# Pure_Keys_aec-pcb3-smd-Vertical-inProgre.net
KiCad netlist of a schematic drawn in EAGLE
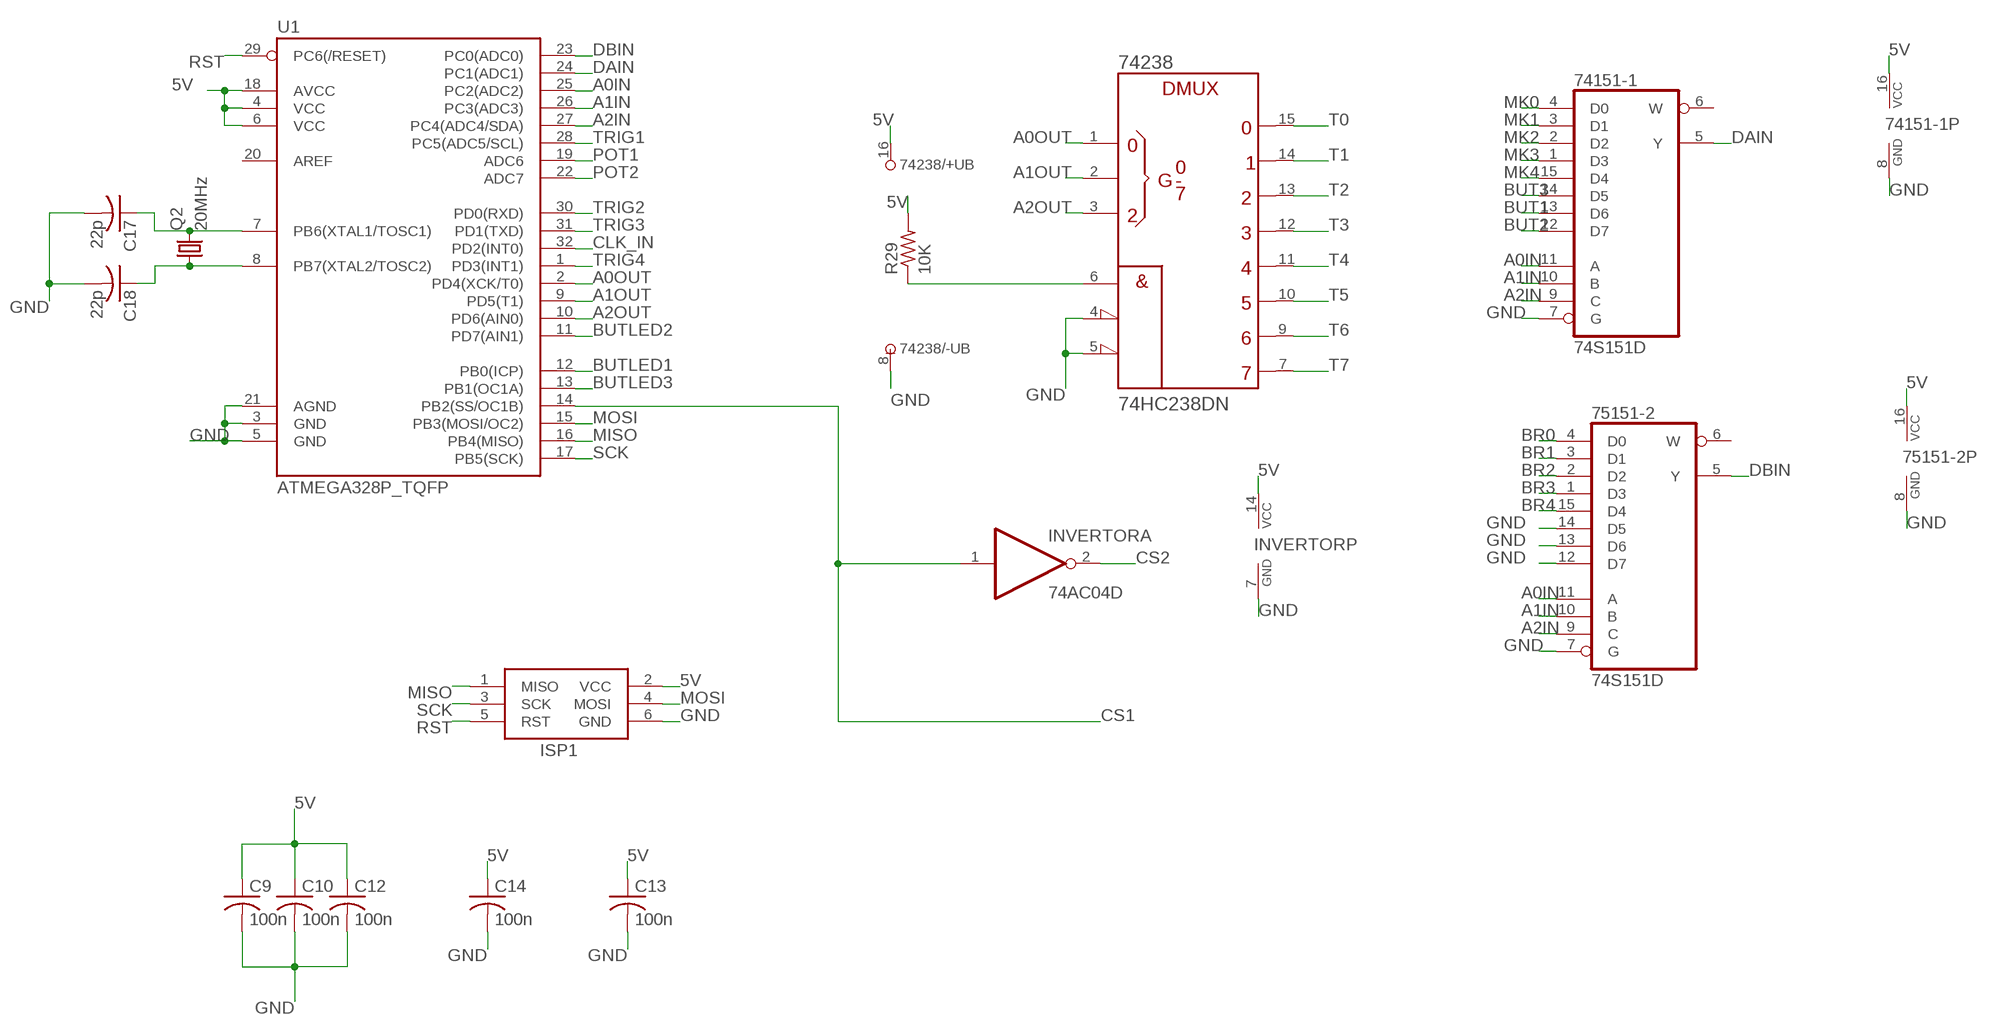
[diagram p0: schematic, sheet 1]
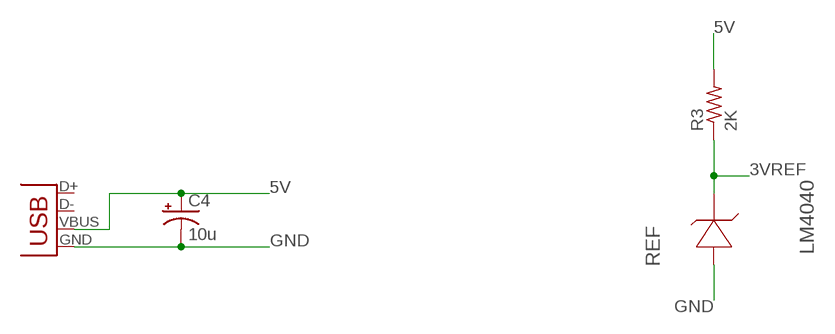
[diagram p1: schematic, sheet 2]
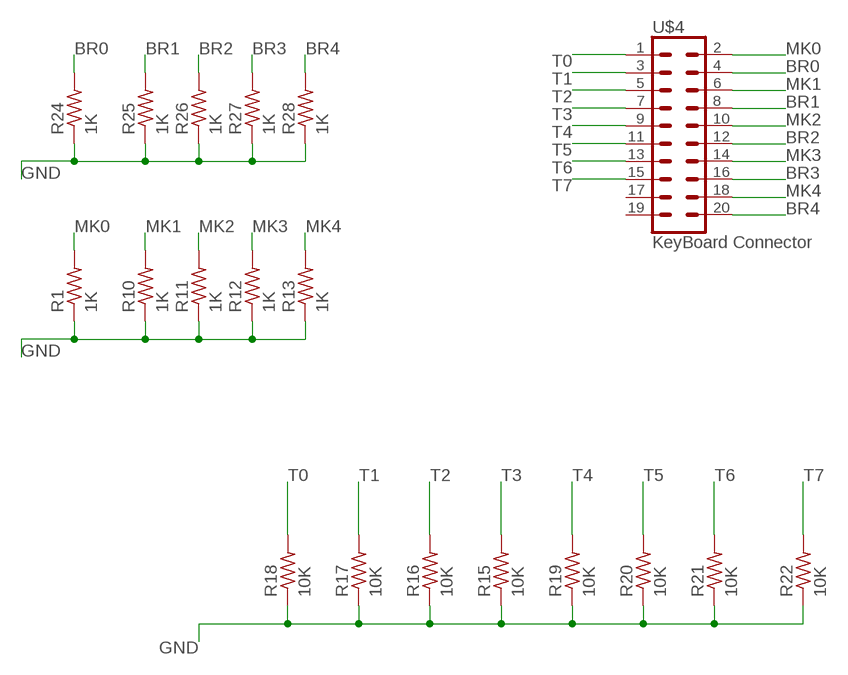
[diagram p2: schematic, sheet 3]
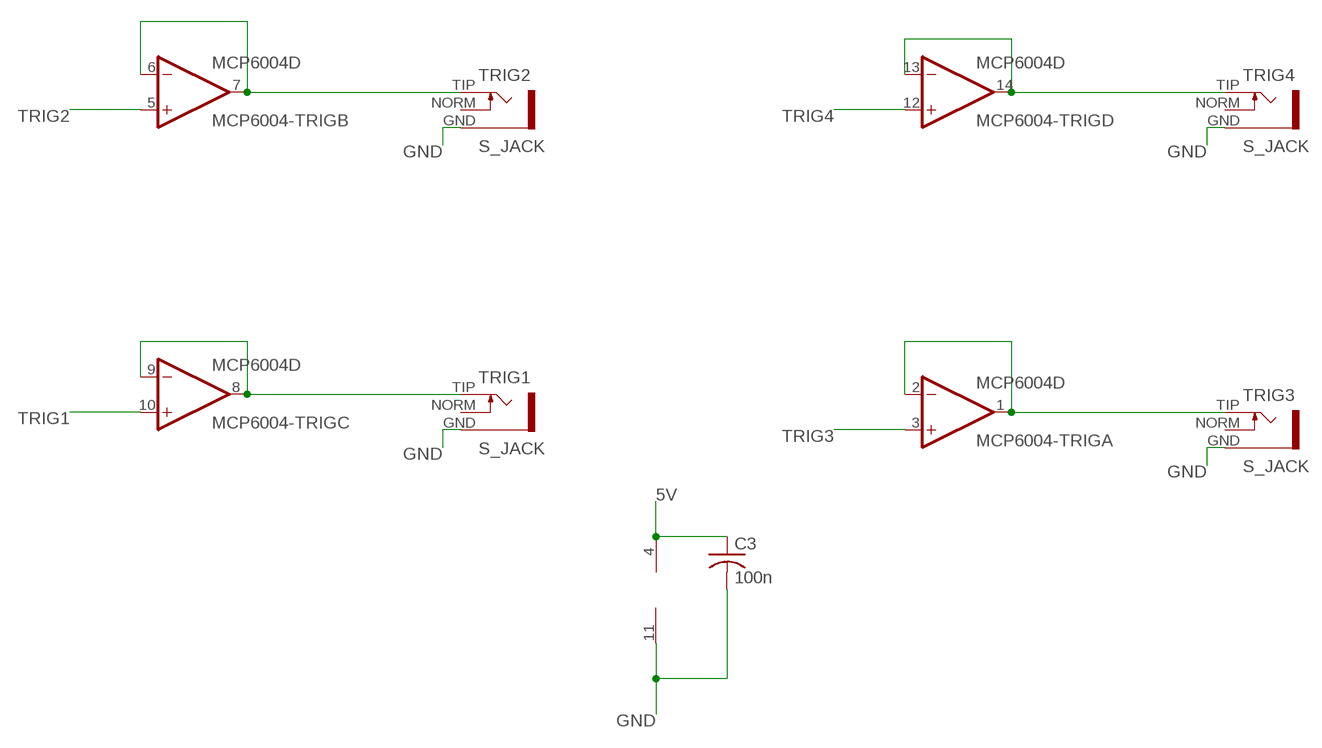
[diagram p3: schematic, sheet 4]
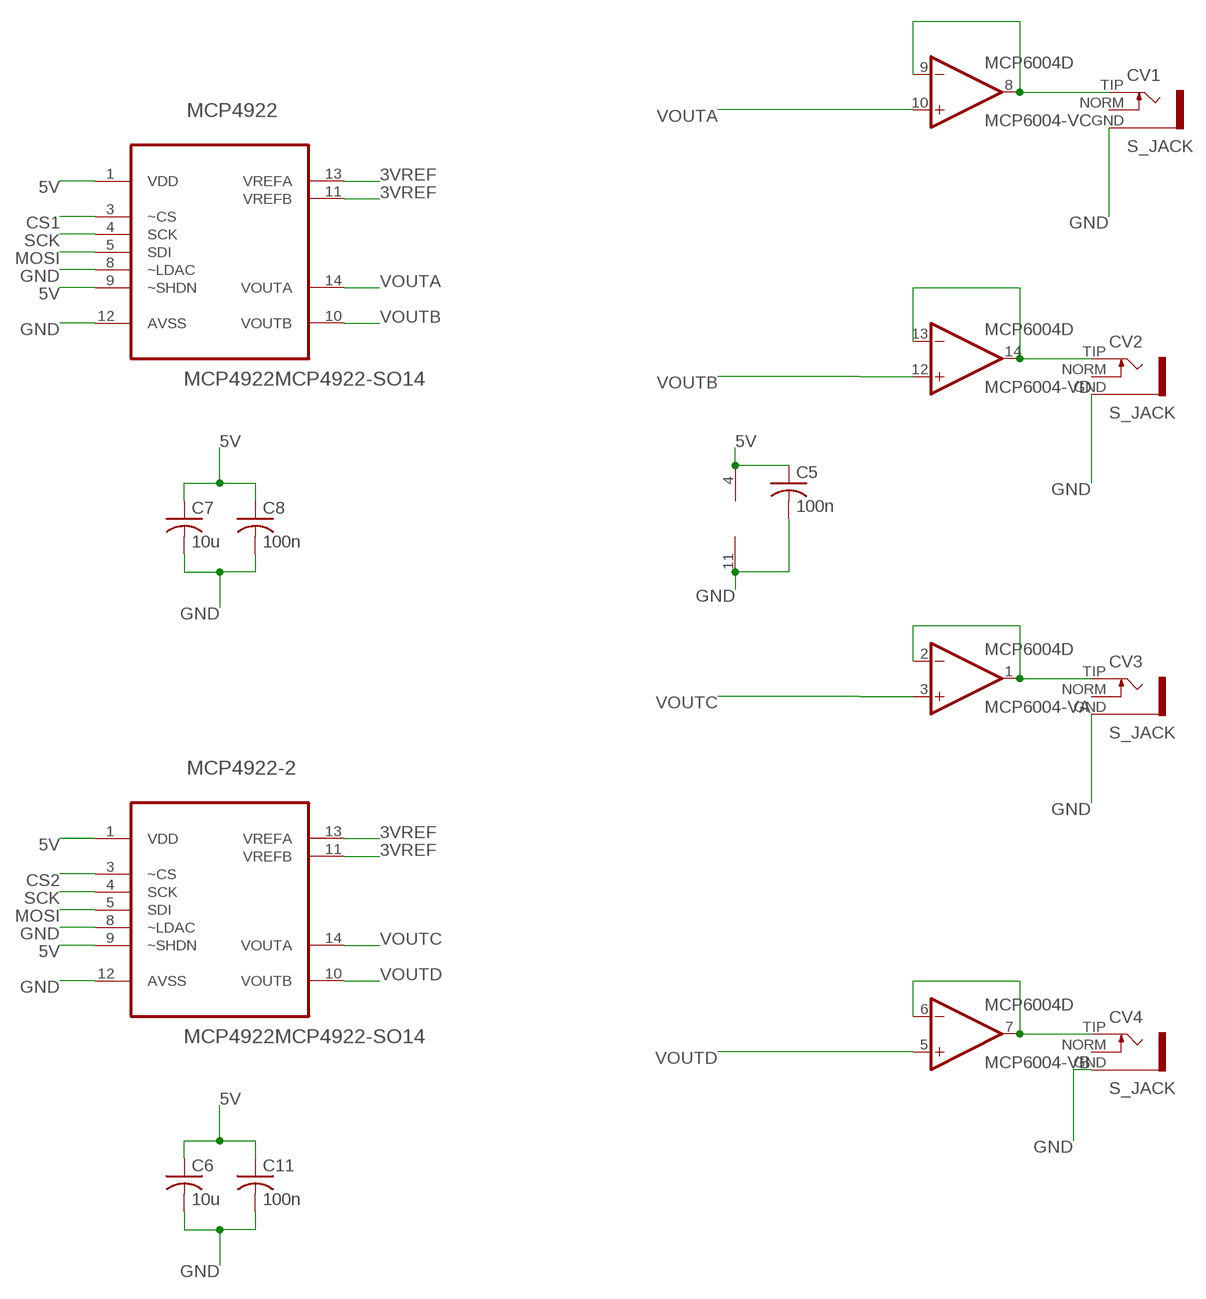
[diagram p4: schematic, sheet 5]
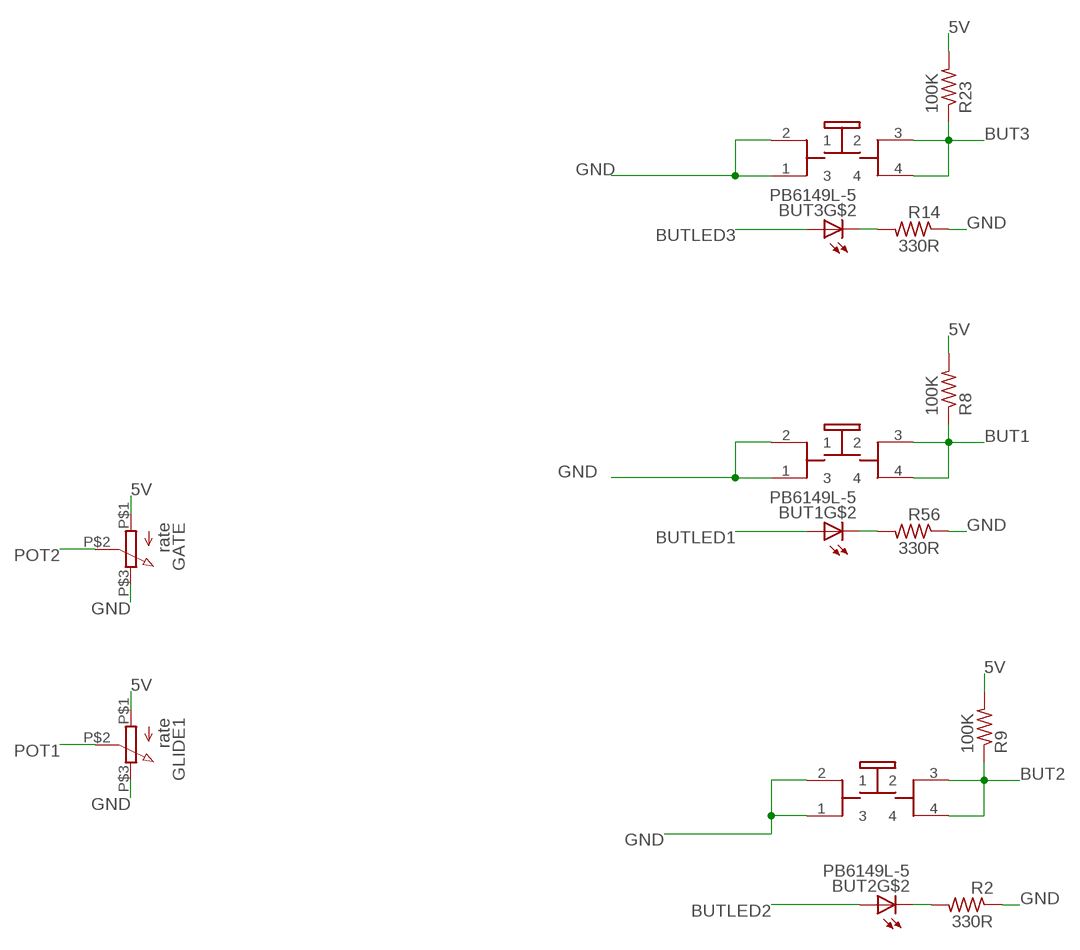
[diagram p5: schematic, sheet 6]
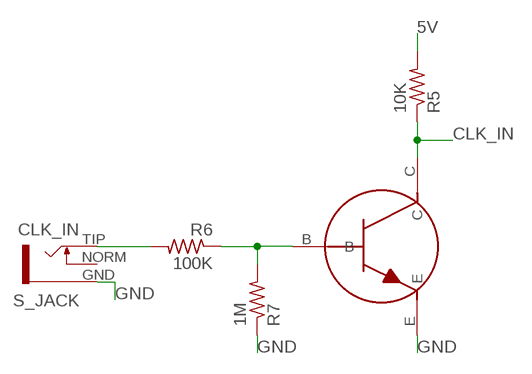
[diagram p6: schematic, sheet 7]

(export (version "E")
  (design (tool "Eeschema 10.0.6"))
  (components
    (comp (ref "C5")
      (value "100n")
      (footprint "eagle-import:C0805K")
      (libsource (lib "eagle-import") (part "C-USC0805K"))
    )
    (comp (ref "C6")
      (value "10u")
      (footprint "eagle-import:C0805K")
      (libsource (lib "eagle-import") (part "C-USC0805K"))
    )
    (comp (ref "C7")
      (value "10u")
      (footprint "eagle-import:C0805K")
      (libsource (lib "eagle-import") (part "C-USC0805K"))
    )
    (comp (ref "C8")
      (value "100n")
      (footprint "eagle-import:C0805K")
      (libsource (lib "eagle-import") (part "C-USC0805K"))
    )
    (comp (ref "C11")
      (value "100n")
      (footprint "eagle-import:C0805K")
      (libsource (lib "eagle-import") (part "C-USC0805K"))
    )
    (comp (ref "CV1")
      (value "S_JACK")
      (footprint "eagle-import:S_JACK")
      (libsource (lib "eagle-import") (part "S_JACK"))
    )
    (comp (ref "CV2")
      (value "S_JACK")
      (footprint "eagle-import:S_JACK")
      (libsource (lib "eagle-import") (part "S_JACK"))
    )
    (comp (ref "CV3")
      (value "S_JACK")
      (footprint "eagle-import:S_JACK")
      (libsource (lib "eagle-import") (part "S_JACK"))
    )
    (comp (ref "CV4")
      (value "S_JACK")
      (footprint "eagle-import:S_JACK")
      (libsource (lib "eagle-import") (part "S_JACK"))
    )
    (comp (ref "MCP4922")
      (value "MCP4922MCP4922-SO14")
      (footprint "eagle-import:SO14")
      (libsource (lib "eagle-import") (part "MCP4922MCP4922-SO14"))
    )
    (comp (ref "MCP4922-2")
      (value "MCP4922MCP4922-SO14")
      (footprint "eagle-import:SO14")
      (libsource (lib "eagle-import") (part "MCP4922MCP4922-SO14"))
    )
    (comp (ref "MCP6004-V")
      (value "MCP6004D")
      (footprint "eagle-import:SO14")
      (libsource (lib "eagle-import") (part "MCP6004D"))
    )
    (comp (ref "74151-1")
      (value "74S151D")
      (footprint "eagle-import:SO16")
      (libsource (lib "eagle-import") (part "74151DS"))
    )
    (comp (ref "74238")
      (value "74HC238DN")
      (footprint "eagle-import:SO16")
      (libsource (lib "eagle-import") (part "74HC238DN"))
    )
    (comp (ref "75151-2")
      (value "74S151D")
      (footprint "eagle-import:SO16")
      (libsource (lib "eagle-import") (part "74151DS"))
    )
    (comp (ref "C9")
      (value "100n")
      (footprint "eagle-import:C0805K")
      (libsource (lib "eagle-import") (part "C-USC0805K"))
    )
    (comp (ref "C10")
      (value "100n")
      (footprint "eagle-import:C0805K")
      (libsource (lib "eagle-import") (part "C-USC0805K"))
    )
    (comp (ref "C12")
      (value "100n")
      (footprint "eagle-import:C0805K")
      (libsource (lib "eagle-import") (part "C-USC0805K"))
    )
    (comp (ref "C13")
      (value "100n")
      (footprint "eagle-import:C0805K")
      (libsource (lib "eagle-import") (part "C-USC0805K"))
    )
    (comp (ref "C14")
      (value "100n")
      (footprint "eagle-import:C0805K")
      (libsource (lib "eagle-import") (part "C-USC0805K"))
    )
    (comp (ref "C17")
      (value "22p")
      (footprint "eagle-import:C0805K")
      (libsource (lib "eagle-import") (part "C-USC0805K"))
    )
    (comp (ref "C18")
      (value "22p")
      (footprint "eagle-import:C0805K")
      (libsource (lib "eagle-import") (part "C-USC0805K"))
    )
    (comp (ref "INVERTOR")
      (value "74AC04D")
      (footprint "eagle-import:SO14")
      (libsource (lib "eagle-import") (part "7404DAC"))
    )
    (comp (ref "ISP1")
      (value "AVRISP-6")
      (footprint "eagle-import:AVRISP")
      (libsource (lib "eagle-import") (part "AVRISP-6"))
    )
    (comp (ref "Q2")
      (value "20MHz")
      (footprint "eagle-import:HC49UP")
      (libsource (lib "eagle-import") (part "CRYSTALHC49UP"))
    )
    (comp (ref "R29")
      (value "10K")
      (footprint "eagle-import:R0805")
      (libsource (lib "eagle-import") (part "R-US_R0805"))
    )
    (comp (ref "U1")
      (value "ATMEGA328P_TQFP")
      (footprint "eagle-import:TQFP32-08")
      (libsource (lib "eagle-import") (part "ATMEGA328P_TQFP"))
    )
    (comp (ref "C4")
      (value "10u")
      (footprint "eagle-import:153CLV-0505")
      (libsource (lib "eagle-import") (part "CPOL-US153CLV-0505"))
    )
    (comp (ref "JP2")
      (value "USB-B")
      (footprint "eagle-import:USB-B-PTH")
      (libsource (lib "eagle-import") (part "USBPTH"))
    )
    (comp (ref "R3")
      (value "2K")
      (footprint "eagle-import:R0805")
      (libsource (lib "eagle-import") (part "R-US_R0805"))
    )
    (comp (ref "REF")
      (value "LM4040")
      (footprint "eagle-import:SOT95P237X112-3N")
      (fields
        (field (name "MPN") "LM4040A50IDBZT")
        (field (name "MPN_1") "LM4040A30IDBZT")
        (field (name "RS-PART") "809-6343")
      )
      (libsource (lib "eagle-import") (part "LM4040A30IDBZT"))
    )
    (comp (ref "CLK_IN")
      (value "S_JACK")
      (footprint "eagle-import:S_JACK")
      (libsource (lib "eagle-import") (part "S_JACK"))
    )
    (comp (ref "CLOCK")
      (value "2N3904")
      (footprint "eagle-import:TRANSISTOR_SINGLE_N-TYPE")
      (libsource (lib "eagle-import") (part "TRANSISTOR_MMBT3904"))
    )
    (comp (ref "R5")
      (value "10K")
      (footprint "eagle-import:R0805")
      (libsource (lib "eagle-import") (part "R-US_R0805"))
    )
    (comp (ref "R6")
      (value "100K")
      (footprint "eagle-import:R0805")
      (libsource (lib "eagle-import") (part "R-US_R0805"))
    )
    (comp (ref "R7")
      (value "1M")
      (footprint "eagle-import:R0805")
      (libsource (lib "eagle-import") (part "R-US_R0805"))
    )
    (comp (ref "R1")
      (value "1K")
      (footprint "eagle-import:R0805")
      (fields (field (name "RS-PART") "223-0427"))
      (libsource (lib "eagle-import") (part "R-US_R0805"))
    )
    (comp (ref "R10")
      (value "1K")
      (footprint "eagle-import:R0805")
      (fields (field (name "RS-PART") "223-0427"))
      (libsource (lib "eagle-import") (part "R-US_R0805"))
    )
    (comp (ref "R11")
      (value "1K")
      (footprint "eagle-import:R0805")
      (fields (field (name "RS-PART") "223-0427"))
      (libsource (lib "eagle-import") (part "R-US_R0805"))
    )
    (comp (ref "R12")
      (value "1K")
      (footprint "eagle-import:R0805")
      (fields (field (name "RS-PART") "223-0427"))
      (libsource (lib "eagle-import") (part "R-US_R0805"))
    )
    (comp (ref "R13")
      (value "1K")
      (footprint "eagle-import:R0805")
      (fields (field (name "RS-PART") "223-0427"))
      (libsource (lib "eagle-import") (part "R-US_R0805"))
    )
    (comp (ref "R15")
      (value "10K")
      (footprint "eagle-import:R0805")
      (libsource (lib "eagle-import") (part "R-US_R0805"))
    )
    (comp (ref "R16")
      (value "10K")
      (footprint "eagle-import:R0805")
      (libsource (lib "eagle-import") (part "R-US_R0805"))
    )
    (comp (ref "R17")
      (value "10K")
      (footprint "eagle-import:R0805")
      (libsource (lib "eagle-import") (part "R-US_R0805"))
    )
    (comp (ref "R18")
      (value "10K")
      (footprint "eagle-import:R0805")
      (libsource (lib "eagle-import") (part "R-US_R0805"))
    )
    (comp (ref "R19")
      (value "10K")
      (footprint "eagle-import:R0805")
      (libsource (lib "eagle-import") (part "R-US_R0805"))
    )
    (comp (ref "R20")
      (value "10K")
      (footprint "eagle-import:R0805")
      (libsource (lib "eagle-import") (part "R-US_R0805"))
    )
    (comp (ref "R21")
      (value "10K")
      (footprint "eagle-import:R0805")
      (libsource (lib "eagle-import") (part "R-US_R0805"))
    )
    (comp (ref "R22")
      (value "10K")
      (footprint "eagle-import:R0805")
      (libsource (lib "eagle-import") (part "R-US_R0805"))
    )
    (comp (ref "R24")
      (value "1K")
      (footprint "eagle-import:R0805")
      (fields (field (name "RS-PART") "223-0427"))
      (libsource (lib "eagle-import") (part "R-US_R0805"))
    )
    (comp (ref "R25")
      (value "1K")
      (footprint "eagle-import:R0805")
      (fields (field (name "RS-PART") "223-0427"))
      (libsource (lib "eagle-import") (part "R-US_R0805"))
    )
    (comp (ref "R26")
      (value "1K")
      (footprint "eagle-import:R0805")
      (fields (field (name "RS-PART") "223-0427"))
      (libsource (lib "eagle-import") (part "R-US_R0805"))
    )
    (comp (ref "R27")
      (value "1K")
      (footprint "eagle-import:R0805")
      (fields (field (name "RS-PART") "223-0427"))
      (libsource (lib "eagle-import") (part "R-US_R0805"))
    )
    (comp (ref "R28")
      (value "1K")
      (footprint "eagle-import:R0805")
      (fields (field (name "RS-PART") "223-0427"))
      (libsource (lib "eagle-import") (part "R-US_R0805"))
    )
    (comp (ref "U$4")
      (value "KeyBoard Connector")
      (footprint "eagle-import:2X10")
      (fields (field (name "RS-PART") "669-5364"))
      (libsource (lib "eagle-import") (part "CONN_10X2"))
    )
    (comp (ref "BUT1")
      (value "PB6149L-5")
      (footprint "eagle-import:PB6149L")
      (libsource (lib "eagle-import") (part "PB6149L-5"))
    )
    (comp (ref "BUT2")
      (value "PB6149L-5")
      (footprint "eagle-import:PB6149L")
      (libsource (lib "eagle-import") (part "PB6149L-5"))
    )
    (comp (ref "BUT3")
      (value "PB6149L-5")
      (footprint "eagle-import:PB6149L")
      (libsource (lib "eagle-import") (part "PB6149L-5"))
    )
    (comp (ref "GATE")
      (value "rate")
      (footprint "eagle-import:POT")
      (libsource (lib "eagle-import") (part "9MMPOT"))
    )
    (comp (ref "GLIDE1")
      (value "rate")
      (footprint "eagle-import:POT")
      (libsource (lib "eagle-import") (part "9MMPOT"))
    )
    (comp (ref "R2")
      (value "330R")
      (footprint "eagle-import:R0805")
      (libsource (lib "eagle-import") (part "R-US_R0805"))
    )
    (comp (ref "R8")
      (value "100K")
      (footprint "eagle-import:R0805")
      (libsource (lib "eagle-import") (part "R-US_R0805"))
    )
    (comp (ref "R9")
      (value "100K")
      (footprint "eagle-import:R0805")
      (libsource (lib "eagle-import") (part "R-US_R0805"))
    )
    (comp (ref "R14")
      (value "330R")
      (footprint "eagle-import:R0805")
      (libsource (lib "eagle-import") (part "R-US_R0805"))
    )
    (comp (ref "R23")
      (value "100K")
      (footprint "eagle-import:R0805")
      (libsource (lib "eagle-import") (part "R-US_R0805"))
    )
    (comp (ref "R56")
      (value "330R")
      (footprint "eagle-import:R0805")
      (libsource (lib "eagle-import") (part "R-US_R0805"))
    )
    (comp (ref "C3")
      (value "100n")
      (footprint "eagle-import:C0805K")
      (libsource (lib "eagle-import") (part "C-USC0805K"))
    )
    (comp (ref "MCP6004-TRIG")
      (value "MCP6004D")
      (footprint "eagle-import:SO14")
      (libsource (lib "eagle-import") (part "MCP6004D"))
    )
    (comp (ref "TRIG1")
      (value "S_JACK")
      (footprint "eagle-import:S_JACK")
      (libsource (lib "eagle-import") (part "S_JACK"))
    )
    (comp (ref "TRIG2")
      (value "S_JACK")
      (footprint "eagle-import:S_JACK")
      (libsource (lib "eagle-import") (part "S_JACK"))
    )
    (comp (ref "TRIG3")
      (value "S_JACK")
      (footprint "eagle-import:S_JACK")
      (libsource (lib "eagle-import") (part "S_JACK"))
    )
    (comp (ref "TRIG4")
      (value "S_JACK")
      (footprint "eagle-import:S_JACK")
      (libsource (lib "eagle-import") (part "S_JACK"))
    )
  )
  (nets
    (net (code "1") (name "3VREF") (class "Default")
      (node (ref "MCP4922") (pin "11") (pinfunction "VREFB_11") (pintype "bidirectional"))
      (node (ref "MCP4922") (pin "13") (pinfunction "VREFA_13") (pintype "input"))
      (node (ref "MCP4922-2") (pin "11") (pinfunction "VREFB_11") (pintype "bidirectional"))
      (node (ref "MCP4922-2") (pin "13") (pinfunction "VREFA_13") (pintype "input"))
      (node (ref "R3") (pin "1") (pinfunction "1_1") (pintype "passive"))
      (node (ref "REF") (pin "1") (pinfunction "CATHODE_1") (pintype "output"))
    )
    (net (code "2") (name "5V") (class "Default")
      (node (ref "74151-1") (pin "16") (pinfunction "VCC_16") (pintype "power_in"))
      (node (ref "74238") (pin "16") (pinfunction "+UB_16") (pintype "power_in"))
      (node (ref "75151-2") (pin "16") (pinfunction "VCC_16") (pintype "power_in"))
      (node (ref "C10") (pin "1") (pinfunction "1_1") (pintype "passive"))
      (node (ref "C11") (pin "1") (pinfunction "1_1") (pintype "passive"))
      (node (ref "C12") (pin "1") (pinfunction "1_1") (pintype "passive"))
      (node (ref "C13") (pin "1") (pinfunction "1_1") (pintype "passive"))
      (node (ref "C14") (pin "1") (pinfunction "1_1") (pintype "passive"))
      (node (ref "C3") (pin "1") (pinfunction "1_1") (pintype "passive"))
      (node (ref "C4") (pin "+") (pinfunction "+_+") (pintype "passive"))
      (node (ref "C5") (pin "1") (pinfunction "1_1") (pintype "passive"))
      (node (ref "C6") (pin "1") (pinfunction "1_1") (pintype "passive"))
      (node (ref "C7") (pin "1") (pinfunction "1_1") (pintype "passive"))
      (node (ref "C8") (pin "1") (pinfunction "1_1") (pintype "passive"))
      (node (ref "C9") (pin "1") (pinfunction "1_1") (pintype "passive"))
      (node (ref "GATE") (pin "P$1") (pinfunction "1_P$1") (pintype "passive"))
      (node (ref "GLIDE1") (pin "P$1") (pinfunction "1_P$1") (pintype "passive"))
      (node (ref "INVERTOR") (pin "14") (pinfunction "VCC_14") (pintype "power_in"))
      (node (ref "ISP1") (pin "2") (pinfunction "VCC_2") (pintype "power_in"))
      (node (ref "JP2") (pin "VBUS") (pinfunction "VBUS_VBUS") (pintype "bidirectional"))
      (node (ref "MCP4922") (pin "1") (pinfunction "VDD_1") (pintype "power_in"))
      (node (ref "MCP4922") (pin "9") (pinfunction "~{SHDN}_9") (pintype "bidirectional"))
      (node (ref "MCP4922-2") (pin "1") (pinfunction "VDD_1") (pintype "power_in"))
      (node (ref "MCP4922-2") (pin "9") (pinfunction "~{SHDN}_9") (pintype "bidirectional"))
      (node (ref "MCP6004-TRIG") (pin "4") (pinfunction "V+_4") (pintype "power_in"))
      (node (ref "MCP6004-V") (pin "4") (pinfunction "V+_4") (pintype "power_in"))
      (node (ref "R23") (pin "2") (pinfunction "2_2") (pintype "passive"))
      (node (ref "R29") (pin "2") (pinfunction "2_2") (pintype "passive"))
      (node (ref "R3") (pin "2") (pinfunction "2_2") (pintype "passive"))
      (node (ref "R5") (pin "2") (pinfunction "2_2") (pintype "passive"))
      (node (ref "R8") (pin "2") (pinfunction "2_2") (pintype "passive"))
      (node (ref "R9") (pin "2") (pinfunction "2_2") (pintype "passive"))
      (node (ref "U1") (pin "18") (pinfunction "AVCC_18") (pintype "bidirectional"))
      (node (ref "U1") (pin "4") (pinfunction "VCC_4") (pintype "bidirectional"))
      (node (ref "U1") (pin "6") (pinfunction "VCC_6") (pintype "bidirectional"))
    )
    (net (code "3") (name "A0IN") (class "Default")
      (node (ref "74151-1") (pin "11") (pinfunction "A_11") (pintype "input"))
      (node (ref "75151-2") (pin "11") (pinfunction "A_11") (pintype "input"))
      (node (ref "U1") (pin "25") (pinfunction "PC2(ADC2)_25") (pintype "bidirectional"))
    )
    (net (code "4") (name "A0OUT") (class "Default")
      (node (ref "74238") (pin "1") (pinfunction "A_1") (pintype "input"))
      (node (ref "U1") (pin "2") (pinfunction "PD4(XCK/T0)_2") (pintype "bidirectional"))
    )
    (net (code "5") (name "A1IN") (class "Default")
      (node (ref "74151-1") (pin "10") (pinfunction "B_10") (pintype "input"))
      (node (ref "75151-2") (pin "10") (pinfunction "B_10") (pintype "input"))
      (node (ref "U1") (pin "26") (pinfunction "PC3(ADC3)_26") (pintype "bidirectional"))
    )
    (net (code "6") (name "A1OUT") (class "Default")
      (node (ref "74238") (pin "2") (pinfunction "B_2") (pintype "input"))
      (node (ref "U1") (pin "9") (pinfunction "PD5(T1)_9") (pintype "bidirectional"))
    )
    (net (code "7") (name "A2IN") (class "Default")
      (node (ref "74151-1") (pin "9") (pinfunction "C_9") (pintype "input"))
      (node (ref "75151-2") (pin "9") (pinfunction "C_9") (pintype "input"))
      (node (ref "U1") (pin "27") (pinfunction "PC4(ADC4/SDA)_27") (pintype "bidirectional"))
    )
    (net (code "8") (name "A2OUT") (class "Default")
      (node (ref "74238") (pin "3") (pinfunction "C_3") (pintype "input"))
      (node (ref "U1") (pin "10") (pinfunction "PD6(AIN0)_10") (pintype "bidirectional"))
    )
    (net (code "9") (name "BR0") (class "Default")
      (node (ref "75151-2") (pin "4") (pinfunction "D0_4") (pintype "input"))
      (node (ref "R24") (pin "2") (pinfunction "2_2") (pintype "passive"))
      (node (ref "U$4") (pin "4") (pinfunction "4_4") (pintype "passive"))
    )
    (net (code "10") (name "BR1") (class "Default")
      (node (ref "75151-2") (pin "3") (pinfunction "D1_3") (pintype "input"))
      (node (ref "R25") (pin "2") (pinfunction "2_2") (pintype "passive"))
      (node (ref "U$4") (pin "8") (pinfunction "8_8") (pintype "passive"))
    )
    (net (code "11") (name "BR2") (class "Default")
      (node (ref "75151-2") (pin "2") (pinfunction "D2_2") (pintype "input"))
      (node (ref "R26") (pin "2") (pinfunction "2_2") (pintype "passive"))
      (node (ref "U$4") (pin "12") (pinfunction "12_12") (pintype "passive"))
    )
    (net (code "12") (name "BR3") (class "Default")
      (node (ref "75151-2") (pin "1") (pinfunction "D3_1") (pintype "input"))
      (node (ref "R27") (pin "2") (pinfunction "2_2") (pintype "passive"))
      (node (ref "U$4") (pin "16") (pinfunction "16_16") (pintype "passive"))
    )
    (net (code "13") (name "BR4") (class "Default")
      (node (ref "75151-2") (pin "15") (pinfunction "D4_15") (pintype "input"))
      (node (ref "R28") (pin "2") (pinfunction "2_2") (pintype "passive"))
      (node (ref "U$4") (pin "20") (pinfunction "20_20") (pintype "passive"))
    )
    (net (code "14") (name "BUT1") (class "Default")
      (node (ref "74151-1") (pin "13") (pinfunction "D6_13") (pintype "input"))
      (node (ref "BUT1") (pin "3") (pinfunction "2_3") (pintype "bidirectional"))
      (node (ref "BUT1") (pin "4") (pinfunction "4_4") (pintype "bidirectional"))
      (node (ref "R8") (pin "1") (pinfunction "1_1") (pintype "passive"))
    )
    (net (code "15") (name "BUT2") (class "Default")
      (node (ref "74151-1") (pin "12") (pinfunction "D7_12") (pintype "input"))
      (node (ref "BUT2") (pin "3") (pinfunction "2_3") (pintype "bidirectional"))
      (node (ref "BUT2") (pin "4") (pinfunction "4_4") (pintype "bidirectional"))
      (node (ref "R9") (pin "1") (pinfunction "1_1") (pintype "passive"))
    )
    (net (code "16") (name "BUT3") (class "Default")
      (node (ref "74151-1") (pin "14") (pinfunction "D5_14") (pintype "input"))
      (node (ref "BUT3") (pin "3") (pinfunction "2_3") (pintype "bidirectional"))
      (node (ref "BUT3") (pin "4") (pinfunction "4_4") (pintype "bidirectional"))
      (node (ref "R23") (pin "1") (pinfunction "1_1") (pintype "passive"))
    )
    (net (code "17") (name "BUTLED1") (class "Default")
      (node (ref "BUT1") (pin "A") (pinfunction "A_A") (pintype "passive"))
      (node (ref "U1") (pin "12") (pinfunction "PB0(ICP)_12") (pintype "bidirectional"))
    )
    (net (code "18") (name "BUTLED2") (class "Default")
      (node (ref "BUT2") (pin "A") (pinfunction "A_A") (pintype "passive"))
      (node (ref "U1") (pin "11") (pinfunction "PD7(AIN1)_11") (pintype "bidirectional"))
    )
    (net (code "19") (name "BUTLED3") (class "Default")
      (node (ref "BUT3") (pin "A") (pinfunction "A_A") (pintype "passive"))
      (node (ref "U1") (pin "13") (pinfunction "PB1(OC1A)_13") (pintype "bidirectional"))
    )
    (net (code "20") (name "CLK_IN") (class "Default")
      (node (ref "CLOCK") (pin "C") (pinfunction "C_C") (pintype "bidirectional"))
      (node (ref "R5") (pin "1") (pinfunction "1_1") (pintype "passive"))
      (node (ref "U1") (pin "32") (pinfunction "PD2(INT0)_32") (pintype "bidirectional"))
    )
    (net (code "21") (name "CS1") (class "Default")
      (node (ref "INVERTOR") (pin "1") (pinfunction "I_1") (pintype "input"))
      (node (ref "MCP4922") (pin "3") (pinfunction "~{CS}_3") (pintype "input"))
      (node (ref "U1") (pin "14") (pinfunction "PB2(SS/OC1B)_14") (pintype "bidirectional"))
    )
    (net (code "22") (name "CS2") (class "Default")
      (node (ref "INVERTOR") (pin "2") (pinfunction "O_2") (pintype "output"))
      (node (ref "MCP4922-2") (pin "3") (pinfunction "~{CS}_3") (pintype "input"))
    )
    (net (code "23") (name "DAIN") (class "Default")
      (node (ref "74151-1") (pin "5") (pinfunction "Y_5") (pintype "output"))
      (node (ref "U1") (pin "24") (pinfunction "PC1(ADC1)_24") (pintype "bidirectional"))
    )
    (net (code "24") (name "DBIN") (class "Default")
      (node (ref "75151-2") (pin "5") (pinfunction "Y_5") (pintype "output"))
      (node (ref "U1") (pin "23") (pinfunction "PC0(ADC0)_23") (pintype "bidirectional"))
    )
    (net (code "25") (name "GND") (class "Default")
      (node (ref "74151-1") (pin "7") (pinfunction "G_7") (pintype "input"))
      (node (ref "74151-1") (pin "8") (pinfunction "GND_8") (pintype "power_in"))
      (node (ref "74238") (pin "4") (pinfunction "~{G2A}_4") (pintype "input"))
      (node (ref "74238") (pin "5") (pinfunction "~{G2B}_5") (pintype "input"))
      (node (ref "74238") (pin "8") (pinfunction "-UB_8") (pintype "power_in"))
      (node (ref "75151-2") (pin "12") (pinfunction "D7_12") (pintype "input"))
      (node (ref "75151-2") (pin "13") (pinfunction "D6_13") (pintype "input"))
      (node (ref "75151-2") (pin "14") (pinfunction "D5_14") (pintype "input"))
      (node (ref "75151-2") (pin "7") (pinfunction "G_7") (pintype "input"))
      (node (ref "75151-2") (pin "8") (pinfunction "GND_8") (pintype "power_in"))
      (node (ref "BUT1") (pin "1") (pinfunction "3_1") (pintype "bidirectional"))
      (node (ref "BUT1") (pin "2") (pinfunction "1_2") (pintype "bidirectional"))
      (node (ref "BUT2") (pin "1") (pinfunction "3_1") (pintype "bidirectional"))
      (node (ref "BUT2") (pin "2") (pinfunction "1_2") (pintype "bidirectional"))
      (node (ref "BUT3") (pin "1") (pinfunction "3_1") (pintype "bidirectional"))
      (node (ref "BUT3") (pin "2") (pinfunction "1_2") (pintype "bidirectional"))
      (node (ref "C10") (pin "2") (pinfunction "2_2") (pintype "passive"))
      (node (ref "C11") (pin "2") (pinfunction "2_2") (pintype "passive"))
      (node (ref "C12") (pin "2") (pinfunction "2_2") (pintype "passive"))
      (node (ref "C13") (pin "2") (pinfunction "2_2") (pintype "passive"))
      (node (ref "C14") (pin "2") (pinfunction "2_2") (pintype "passive"))
      (node (ref "C17") (pin "2") (pinfunction "2_2") (pintype "passive"))
      (node (ref "C18") (pin "2") (pinfunction "2_2") (pintype "passive"))
      (node (ref "C3") (pin "2") (pinfunction "2_2") (pintype "passive"))
      (node (ref "C4") (pin "-") (pinfunction "-_-") (pintype "passive"))
      (node (ref "C5") (pin "2") (pinfunction "2_2") (pintype "passive"))
      (node (ref "C6") (pin "2") (pinfunction "2_2") (pintype "passive"))
      (node (ref "C7") (pin "2") (pinfunction "2_2") (pintype "passive"))
      (node (ref "C8") (pin "2") (pinfunction "2_2") (pintype "passive"))
      (node (ref "C9") (pin "2") (pinfunction "2_2") (pintype "passive"))
      (node (ref "CLK_IN") (pin "GND") (pinfunction "GND_GND") (pintype "passive"))
      (node (ref "CLOCK") (pin "E") (pinfunction "E_E") (pintype "bidirectional"))
      (node (ref "CV1") (pin "GND") (pinfunction "GND_GND") (pintype "passive"))
      (node (ref "CV2") (pin "GND") (pinfunction "GND_GND") (pintype "passive"))
      (node (ref "CV3") (pin "GND") (pinfunction "GND_GND") (pintype "passive"))
      (node (ref "CV4") (pin "GND") (pinfunction "GND_GND") (pintype "passive"))
      (node (ref "GATE") (pin "P$3") (pinfunction "3_P$3") (pintype "passive"))
      (node (ref "GLIDE1") (pin "P$3") (pinfunction "3_P$3") (pintype "passive"))
      (node (ref "INVERTOR") (pin "7") (pinfunction "GND_7") (pintype "power_in"))
      (node (ref "ISP1") (pin "6") (pinfunction "GND_6") (pintype "power_in"))
      (node (ref "JP2") (pin "GND") (pinfunction "GND_GND") (pintype "bidirectional"))
      (node (ref "MCP4922") (pin "12") (pinfunction "AVSS_12") (pintype "passive"))
      (node (ref "MCP4922") (pin "8") (pinfunction "~{LDAC}_8") (pintype "input"))
      (node (ref "MCP4922-2") (pin "12") (pinfunction "AVSS_12") (pintype "passive"))
      (node (ref "MCP4922-2") (pin "8") (pinfunction "~{LDAC}_8") (pintype "input"))
      (node (ref "MCP6004-TRIG") (pin "11") (pinfunction "V-_11") (pintype "power_in"))
      (node (ref "MCP6004-V") (pin "11") (pinfunction "V-_11") (pintype "power_in"))
      (node (ref "R1") (pin "1") (pinfunction "1_1") (pintype "passive"))
      (node (ref "R10") (pin "1") (pinfunction "1_1") (pintype "passive"))
      (node (ref "R11") (pin "1") (pinfunction "1_1") (pintype "passive"))
      (node (ref "R12") (pin "1") (pinfunction "1_1") (pintype "passive"))
      (node (ref "R13") (pin "1") (pinfunction "1_1") (pintype "passive"))
      (node (ref "R14") (pin "1") (pinfunction "1_1") (pintype "passive"))
      (node (ref "R15") (pin "1") (pinfunction "1_1") (pintype "passive"))
      (node (ref "R16") (pin "1") (pinfunction "1_1") (pintype "passive"))
      (node (ref "R17") (pin "1") (pinfunction "1_1") (pintype "passive"))
      (node (ref "R18") (pin "1") (pinfunction "1_1") (pintype "passive"))
      (node (ref "R19") (pin "1") (pinfunction "1_1") (pintype "passive"))
      (node (ref "R2") (pin "1") (pinfunction "1_1") (pintype "passive"))
      (node (ref "R20") (pin "1") (pinfunction "1_1") (pintype "passive"))
      (node (ref "R21") (pin "1") (pinfunction "1_1") (pintype "passive"))
      (node (ref "R22") (pin "1") (pinfunction "1_1") (pintype "passive"))
      (node (ref "R24") (pin "1") (pinfunction "1_1") (pintype "passive"))
      (node (ref "R25") (pin "1") (pinfunction "1_1") (pintype "passive"))
      (node (ref "R26") (pin "1") (pinfunction "1_1") (pintype "passive"))
      (node (ref "R27") (pin "1") (pinfunction "1_1") (pintype "passive"))
      (node (ref "R28") (pin "1") (pinfunction "1_1") (pintype "passive"))
      (node (ref "R56") (pin "1") (pinfunction "1_1") (pintype "passive"))
      (node (ref "R7") (pin "1") (pinfunction "1_1") (pintype "passive"))
      (node (ref "REF") (pin "2") (pinfunction "ANODE_2") (pintype "input"))
      (node (ref "TRIG1") (pin "GND") (pinfunction "GND_GND") (pintype "passive"))
      (node (ref "TRIG2") (pin "GND") (pinfunction "GND_GND") (pintype "passive"))
      (node (ref "TRIG3") (pin "GND") (pinfunction "GND_GND") (pintype "passive"))
      (node (ref "TRIG4") (pin "GND") (pinfunction "GND_GND") (pintype "passive"))
      (node (ref "U1") (pin "21") (pinfunction "AGND_21") (pintype "bidirectional"))
      (node (ref "U1") (pin "3") (pinfunction "GND_3") (pintype "bidirectional"))
      (node (ref "U1") (pin "5") (pinfunction "GND_5") (pintype "bidirectional"))
    )
    (net (code "26") (name "MISO") (class "Default")
      (node (ref "ISP1") (pin "1") (pinfunction "MISO_1") (pintype "input"))
      (node (ref "U1") (pin "16") (pinfunction "PB4(MISO)_16") (pintype "bidirectional"))
    )
    (net (code "27") (name "MK0") (class "Default")
      (node (ref "74151-1") (pin "4") (pinfunction "D0_4") (pintype "input"))
      (node (ref "R1") (pin "2") (pinfunction "2_2") (pintype "passive"))
      (node (ref "U$4") (pin "2") (pinfunction "2_2") (pintype "passive"))
    )
    (net (code "28") (name "MK1") (class "Default")
      (node (ref "74151-1") (pin "3") (pinfunction "D1_3") (pintype "input"))
      (node (ref "R10") (pin "2") (pinfunction "2_2") (pintype "passive"))
      (node (ref "U$4") (pin "6") (pinfunction "6_6") (pintype "passive"))
    )
    (net (code "29") (name "MK2") (class "Default")
      (node (ref "74151-1") (pin "2") (pinfunction "D2_2") (pintype "input"))
      (node (ref "R11") (pin "2") (pinfunction "2_2") (pintype "passive"))
      (node (ref "U$4") (pin "10") (pinfunction "10_10") (pintype "passive"))
    )
    (net (code "30") (name "MK3") (class "Default")
      (node (ref "74151-1") (pin "1") (pinfunction "D3_1") (pintype "input"))
      (node (ref "R12") (pin "2") (pinfunction "2_2") (pintype "passive"))
      (node (ref "U$4") (pin "14") (pinfunction "14_14") (pintype "passive"))
    )
    (net (code "31") (name "MK4") (class "Default")
      (node (ref "74151-1") (pin "15") (pinfunction "D4_15") (pintype "input"))
      (node (ref "R13") (pin "2") (pinfunction "2_2") (pintype "passive"))
      (node (ref "U$4") (pin "18") (pinfunction "18_18") (pintype "passive"))
    )
    (net (code "32") (name "MOSI") (class "Default")
      (node (ref "ISP1") (pin "4") (pinfunction "MOSI_4") (pintype "output"))
      (node (ref "MCP4922") (pin "5") (pinfunction "SDI_5") (pintype "input"))
      (node (ref "MCP4922-2") (pin "5") (pinfunction "SDI_5") (pintype "input"))
      (node (ref "U1") (pin "15") (pinfunction "PB3(MOSI/OC2)_15") (pintype "bidirectional"))
    )
    (net (code "33") (name "Net-(74238C-G1)") (class "Default")
      (node (ref "74238") (pin "6") (pinfunction "G1_6") (pintype "input"))
      (node (ref "R29") (pin "1") (pinfunction "1_1") (pintype "passive"))
    )
    (net (code "34") (name "Net-(BUT1B-C)") (class "Default")
      (node (ref "BUT1") (pin "K") (pinfunction "C_K") (pintype "passive"))
      (node (ref "R56") (pin "2") (pinfunction "2_2") (pintype "passive"))
    )
    (net (code "35") (name "Net-(BUT2B-C)") (class "Default")
      (node (ref "BUT2") (pin "K") (pinfunction "C_K") (pintype "passive"))
      (node (ref "R2") (pin "2") (pinfunction "2_2") (pintype "passive"))
    )
    (net (code "36") (name "Net-(BUT3B-C)") (class "Default")
      (node (ref "BUT3") (pin "K") (pinfunction "C_K") (pintype "passive"))
      (node (ref "R14") (pin "2") (pinfunction "2_2") (pintype "passive"))
    )
    (net (code "37") (name "Net-(CLK_IN-PadTIP)") (class "Default")
      (node (ref "CLK_IN") (pin "TIP") (pinfunction "TIP_TIP") (pintype "passive"))
      (node (ref "R6") (pin "2") (pinfunction "2_2") (pintype "passive"))
    )
    (net (code "38") (name "Net-(CLOCK-PadB)") (class "Default")
      (node (ref "CLOCK") (pin "B") (pinfunction "B_B") (pintype "bidirectional"))
      (node (ref "R6") (pin "1") (pinfunction "1_1") (pintype "passive"))
      (node (ref "R7") (pin "2") (pinfunction "2_2") (pintype "passive"))
    )
    (net (code "39") (name "Net-(MCP6004-TRIGA--IN)") (class "Default")
      (node (ref "MCP6004-TRIG") (pin "1") (pinfunction "OUT_1") (pintype "output"))
      (node (ref "MCP6004-TRIG") (pin "2") (pinfunction "-IN_2") (pintype "input"))
      (node (ref "TRIG3") (pin "TIP") (pinfunction "TIP_TIP") (pintype "passive"))
    )
    (net (code "40") (name "Net-(MCP6004-TRIGB--IN)") (class "Default")
      (node (ref "MCP6004-TRIG") (pin "6") (pinfunction "-IN_6") (pintype "input"))
      (node (ref "MCP6004-TRIG") (pin "7") (pinfunction "OUT_7") (pintype "output"))
      (node (ref "TRIG2") (pin "TIP") (pinfunction "TIP_TIP") (pintype "passive"))
    )
    (net (code "41") (name "Net-(MCP6004-TRIGC--IN)") (class "Default")
      (node (ref "MCP6004-TRIG") (pin "8") (pinfunction "OUT_8") (pintype "output"))
      (node (ref "MCP6004-TRIG") (pin "9") (pinfunction "-IN_9") (pintype "input"))
      (node (ref "TRIG1") (pin "TIP") (pinfunction "TIP_TIP") (pintype "passive"))
    )
    (net (code "42") (name "Net-(MCP6004-TRIGD--IN)") (class "Default")
      (node (ref "MCP6004-TRIG") (pin "13") (pinfunction "-IN_13") (pintype "input"))
      (node (ref "MCP6004-TRIG") (pin "14") (pinfunction "OUT_14") (pintype "output"))
      (node (ref "TRIG4") (pin "TIP") (pinfunction "TIP_TIP") (pintype "passive"))
    )
    (net (code "43") (name "Net-(MCP6004-VA--IN)") (class "Default")
      (node (ref "CV3") (pin "TIP") (pinfunction "TIP_TIP") (pintype "passive"))
      (node (ref "MCP6004-V") (pin "1") (pinfunction "OUT_1") (pintype "output"))
      (node (ref "MCP6004-V") (pin "2") (pinfunction "-IN_2") (pintype "input"))
    )
    (net (code "44") (name "Net-(MCP6004-VB--IN)") (class "Default")
      (node (ref "CV4") (pin "TIP") (pinfunction "TIP_TIP") (pintype "passive"))
      (node (ref "MCP6004-V") (pin "6") (pinfunction "-IN_6") (pintype "input"))
      (node (ref "MCP6004-V") (pin "7") (pinfunction "OUT_7") (pintype "output"))
    )
    (net (code "45") (name "Net-(MCP6004-VC--IN)") (class "Default")
      (node (ref "CV1") (pin "TIP") (pinfunction "TIP_TIP") (pintype "passive"))
      (node (ref "MCP6004-V") (pin "8") (pinfunction "OUT_8") (pintype "output"))
      (node (ref "MCP6004-V") (pin "9") (pinfunction "-IN_9") (pintype "input"))
    )
    (net (code "46") (name "Net-(MCP6004-VD--IN)") (class "Default")
      (node (ref "CV2") (pin "TIP") (pinfunction "TIP_TIP") (pintype "passive"))
      (node (ref "MCP6004-V") (pin "13") (pinfunction "-IN_13") (pintype "input"))
      (node (ref "MCP6004-V") (pin "14") (pinfunction "OUT_14") (pintype "output"))
    )
    (net (code "47") (name "Net-(U1-PB6(XTAL1{slash}TOSC1))") (class "Default")
      (node (ref "C17") (pin "1") (pinfunction "1_1") (pintype "passive"))
      (node (ref "Q2") (pin "2") (pinfunction "2_2") (pintype "passive"))
      (node (ref "U1") (pin "7") (pinfunction "PB6(XTAL1/TOSC1)_7") (pintype "bidirectional"))
    )
    (net (code "48") (name "Net-(U1-PB7(XTAL2{slash}TOSC2))") (class "Default")
      (node (ref "C18") (pin "1") (pinfunction "1_1") (pintype "passive"))
      (node (ref "Q2") (pin "1") (pinfunction "1_1") (pintype "passive"))
      (node (ref "U1") (pin "8") (pinfunction "PB7(XTAL2/TOSC2)_8") (pintype "bidirectional"))
    )
    (net (code "49") (name "POT1") (class "Default")
      (node (ref "GLIDE1") (pin "P$2") (pinfunction "2_P$2") (pintype "passive"))
      (node (ref "U1") (pin "19") (pinfunction "ADC6_19") (pintype "bidirectional"))
    )
    (net (code "50") (name "POT2") (class "Default")
      (node (ref "GATE") (pin "P$2") (pinfunction "2_P$2") (pintype "passive"))
      (node (ref "U1") (pin "22") (pinfunction "ADC7_22") (pintype "bidirectional"))
    )
    (net (code "51") (name "RST") (class "Default")
      (node (ref "ISP1") (pin "5") (pinfunction "RST_5") (pintype "output"))
      (node (ref "U1") (pin "29") (pinfunction "PC6(/RESET)_29") (pintype "bidirectional"))
    )
    (net (code "52") (name "SCK") (class "Default")
      (node (ref "ISP1") (pin "3") (pinfunction "SCK_3") (pintype "output"))
      (node (ref "MCP4922") (pin "4") (pinfunction "SCK_4") (pintype "input"))
      (node (ref "MCP4922-2") (pin "4") (pinfunction "SCK_4") (pintype "input"))
      (node (ref "U1") (pin "17") (pinfunction "PB5(SCK)_17") (pintype "bidirectional"))
    )
    (net (code "53") (name "T0") (class "Default")
      (node (ref "74238") (pin "15") (pinfunction "Y0_15") (pintype "output"))
      (node (ref "R18") (pin "2") (pinfunction "2_2") (pintype "passive"))
      (node (ref "U$4") (pin "1") (pinfunction "1_1") (pintype "passive"))
    )
    (net (code "54") (name "T1") (class "Default")
      (node (ref "74238") (pin "14") (pinfunction "Y1_14") (pintype "output"))
      (node (ref "R17") (pin "2") (pinfunction "2_2") (pintype "passive"))
      (node (ref "U$4") (pin "3") (pinfunction "3_3") (pintype "passive"))
    )
    (net (code "55") (name "T2") (class "Default")
      (node (ref "74238") (pin "13") (pinfunction "Y2_13") (pintype "output"))
      (node (ref "R16") (pin "2") (pinfunction "2_2") (pintype "passive"))
      (node (ref "U$4") (pin "5") (pinfunction "5_5") (pintype "passive"))
    )
    (net (code "56") (name "T3") (class "Default")
      (node (ref "74238") (pin "12") (pinfunction "Y3_12") (pintype "output"))
      (node (ref "R15") (pin "2") (pinfunction "2_2") (pintype "passive"))
      (node (ref "U$4") (pin "7") (pinfunction "7_7") (pintype "passive"))
    )
    (net (code "57") (name "T4") (class "Default")
      (node (ref "74238") (pin "11") (pinfunction "Y4_11") (pintype "output"))
      (node (ref "R19") (pin "2") (pinfunction "2_2") (pintype "passive"))
      (node (ref "U$4") (pin "9") (pinfunction "9_9") (pintype "passive"))
    )
    (net (code "58") (name "T5") (class "Default")
      (node (ref "74238") (pin "10") (pinfunction "Y5_10") (pintype "output"))
      (node (ref "R20") (pin "2") (pinfunction "2_2") (pintype "passive"))
      (node (ref "U$4") (pin "11") (pinfunction "11_11") (pintype "passive"))
    )
    (net (code "59") (name "T6") (class "Default")
      (node (ref "74238") (pin "9") (pinfunction "Y6_9") (pintype "output"))
      (node (ref "R21") (pin "2") (pinfunction "2_2") (pintype "passive"))
      (node (ref "U$4") (pin "13") (pinfunction "13_13") (pintype "passive"))
    )
    (net (code "60") (name "T7") (class "Default")
      (node (ref "74238") (pin "7") (pinfunction "Y7_7") (pintype "output"))
      (node (ref "R22") (pin "2") (pinfunction "2_2") (pintype "passive"))
      (node (ref "U$4") (pin "15") (pinfunction "15_15") (pintype "passive"))
    )
    (net (code "61") (name "TRIG1") (class "Default")
      (node (ref "MCP6004-TRIG") (pin "10") (pinfunction "+IN_10") (pintype "input"))
      (node (ref "U1") (pin "28") (pinfunction "PC5(ADC5/SCL)_28") (pintype "bidirectional"))
    )
    (net (code "62") (name "TRIG2") (class "Default")
      (node (ref "MCP6004-TRIG") (pin "5") (pinfunction "+IN_5") (pintype "input"))
      (node (ref "U1") (pin "30") (pinfunction "PD0(RXD)_30") (pintype "bidirectional"))
    )
    (net (code "63") (name "TRIG3") (class "Default")
      (node (ref "MCP6004-TRIG") (pin "3") (pinfunction "+IN_3") (pintype "input"))
      (node (ref "U1") (pin "31") (pinfunction "PD1(TXD)_31") (pintype "bidirectional"))
    )
    (net (code "64") (name "TRIG4") (class "Default")
      (node (ref "MCP6004-TRIG") (pin "12") (pinfunction "+IN_12") (pintype "input"))
      (node (ref "U1") (pin "1") (pinfunction "PD3(INT1)_1") (pintype "bidirectional"))
    )
    (net (code "65") (name "VOUTA") (class "Default")
      (node (ref "MCP4922") (pin "14") (pinfunction "VOUTA_14") (pintype "output"))
      (node (ref "MCP6004-V") (pin "10") (pinfunction "+IN_10") (pintype "input"))
    )
    (net (code "66") (name "VOUTB") (class "Default")
      (node (ref "MCP4922") (pin "10") (pinfunction "VOUTB_10") (pintype "output"))
      (node (ref "MCP6004-V") (pin "12") (pinfunction "+IN_12") (pintype "input"))
    )
    (net (code "67") (name "VOUTC") (class "Default")
      (node (ref "MCP4922-2") (pin "14") (pinfunction "VOUTA_14") (pintype "output"))
      (node (ref "MCP6004-V") (pin "3") (pinfunction "+IN_3") (pintype "input"))
    )
    (net (code "68") (name "VOUTD") (class "Default")
      (node (ref "MCP4922-2") (pin "10") (pinfunction "VOUTB_10") (pintype "output"))
      (node (ref "MCP6004-V") (pin "5") (pinfunction "+IN_5") (pintype "input"))
    )
    (net (code "69") (name "unconnected-(74151-1A-W-Pad6)") (class "Default")
      (node (ref "74151-1") (pin "6") (pinfunction "W_6") (pintype "output"))
    )
    (net (code "70") (name "unconnected-(75151-2A-W-Pad6)") (class "Default")
      (node (ref "75151-2") (pin "6") (pinfunction "W_6") (pintype "output"))
    )
    (net (code "71") (name "unconnected-(CLK_IN-PadNORM)") (class "Default")
      (node (ref "CLK_IN") (pin "NORM") (pinfunction "NORM_NORM") (pintype "passive"))
    )
    (net (code "72") (name "unconnected-(CV1-PadNORM)") (class "Default")
      (node (ref "CV1") (pin "NORM") (pinfunction "NORM_NORM") (pintype "passive"))
    )
    (net (code "73") (name "unconnected-(CV2-PadNORM)") (class "Default")
      (node (ref "CV2") (pin "NORM") (pinfunction "NORM_NORM") (pintype "passive"))
    )
    (net (code "74") (name "unconnected-(CV3-PadNORM)") (class "Default")
      (node (ref "CV3") (pin "NORM") (pinfunction "NORM_NORM") (pintype "passive"))
    )
    (net (code "75") (name "unconnected-(CV4-PadNORM)") (class "Default")
      (node (ref "CV4") (pin "NORM") (pinfunction "NORM_NORM") (pintype "passive"))
    )
    (net (code "76") (name "unconnected-(JP2-PadD+)") (class "Default")
      (node (ref "JP2") (pin "D+") (pinfunction "D+_D+") (pintype "bidirectional"))
    )
    (net (code "77") (name "unconnected-(JP2-PadD-)") (class "Default")
      (node (ref "JP2") (pin "D-") (pinfunction "D-_D-") (pintype "bidirectional"))
    )
    (net (code "78") (name "unconnected-(REF-NC-Pad3)") (class "Default")
      (node (ref "REF") (pin "3") (pinfunction "NC_3") (pintype "no_connect"))
    )
    (net (code "79") (name "unconnected-(TRIG1-PadNORM)") (class "Default")
      (node (ref "TRIG1") (pin "NORM") (pinfunction "NORM_NORM") (pintype "passive"))
    )
    (net (code "80") (name "unconnected-(TRIG2-PadNORM)") (class "Default")
      (node (ref "TRIG2") (pin "NORM") (pinfunction "NORM_NORM") (pintype "passive"))
    )
    (net (code "81") (name "unconnected-(TRIG3-PadNORM)") (class "Default")
      (node (ref "TRIG3") (pin "NORM") (pinfunction "NORM_NORM") (pintype "passive"))
    )
    (net (code "82") (name "unconnected-(TRIG4-PadNORM)") (class "Default")
      (node (ref "TRIG4") (pin "NORM") (pinfunction "NORM_NORM") (pintype "passive"))
    )
    (net (code "83") (name "unconnected-(U$4-Pad17)") (class "Default")
      (node (ref "U$4") (pin "17") (pinfunction "17_17") (pintype "passive"))
    )
    (net (code "84") (name "unconnected-(U$4-Pad19)") (class "Default")
      (node (ref "U$4") (pin "19") (pinfunction "19_19") (pintype "passive"))
    )
    (net (code "85") (name "unconnected-(U1-AREF-Pad20)") (class "Default")
      (node (ref "U1") (pin "20") (pinfunction "AREF_20") (pintype "bidirectional"))
    )
  )
)
